# SCH_switches.net
KiCad netlist of a schematic drawn in Altium Designer
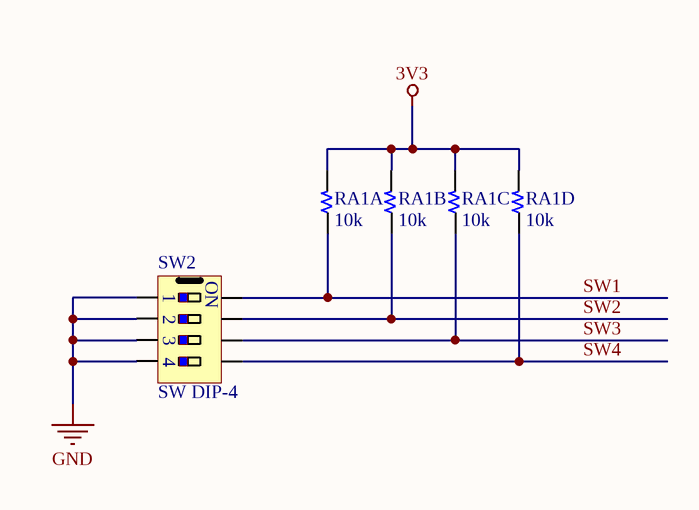
[diagram p0: SCH_switches.SchDoc]

(export (version "E")
  (design (tool "Eeschema 10.0.6"))
  (components
    (comp (ref "RA1A")
      (value "10k")
      (footprint "R 0805")
      (description "Resistor")
      (libsource (lib "chipfc_libs") (part "Resistor"))
    )
    (comp (ref "RA1B")
      (value "10k")
      (footprint "R 0805")
      (description "Resistor")
      (libsource (lib "chipfc_libs") (part "Resistor"))
    )
    (comp (ref "RA1C")
      (value "10k")
      (footprint "R 0805")
      (description "Resistor")
      (libsource (lib "chipfc_libs") (part "Resistor"))
    )
    (comp (ref "RA1D")
      (value "10k")
      (footprint "R 0805")
      (description "Resistor")
      (libsource (lib "chipfc_libs") (part "Resistor"))
    )
    (comp (ref "SW2")
      (value "SW DIP-4")
      (footprint "SW/DIP4")
      (libsource (lib "chipfc_libs") (part "SW DIP-4"))
    )
  )
  (nets
    (net (code "1") (name "/SW1") (class "Default")
      (node (ref "RA1A") (pin "1") (pinfunction "1_1") (pintype "passive"))
      (node (ref "SW2") (pin "8") (pinfunction "8_8") (pintype "passive"))
    )
    (net (code "2") (name "/SW2") (class "Default")
      (node (ref "RA1B") (pin "1") (pinfunction "1_1") (pintype "passive"))
      (node (ref "SW2") (pin "7") (pinfunction "7_7") (pintype "passive"))
    )
    (net (code "3") (name "/SW3") (class "Default")
      (node (ref "RA1C") (pin "1") (pinfunction "1_1") (pintype "passive"))
      (node (ref "SW2") (pin "6") (pinfunction "6_6") (pintype "passive"))
    )
    (net (code "4") (name "/SW4") (class "Default")
      (node (ref "RA1D") (pin "1") (pinfunction "1_1") (pintype "passive"))
      (node (ref "SW2") (pin "5") (pinfunction "5_5") (pintype "passive"))
    )
    (net (code "5") (name "3V3") (class "Default")
      (node (ref "RA1A") (pin "2") (pinfunction "2_2") (pintype "passive"))
      (node (ref "RA1B") (pin "2") (pinfunction "2_2") (pintype "passive"))
      (node (ref "RA1C") (pin "2") (pinfunction "2_2") (pintype "passive"))
      (node (ref "RA1D") (pin "2") (pinfunction "2_2") (pintype "passive"))
    )
    (net (code "6") (name "GND") (class "Default")
      (node (ref "SW2") (pin "1") (pinfunction "1_1") (pintype "passive"))
      (node (ref "SW2") (pin "2") (pinfunction "2_2") (pintype "passive"))
      (node (ref "SW2") (pin "3") (pinfunction "3_3") (pintype "passive"))
      (node (ref "SW2") (pin "4") (pinfunction "4_4") (pintype "passive"))
    )
  )
)
